# untitled.net
KiCad netlist of a schematic drawn in EAGLE
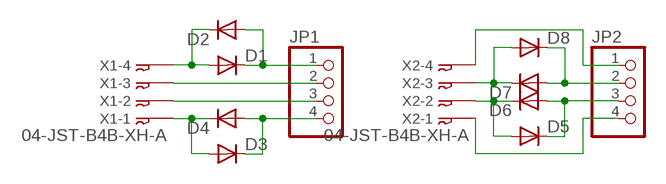
[diagram p0: schematic, sheet 1]

(export (version "E")
  (design (tool "Eeschema 10.0.6"))
  (components
    (comp (ref "D1")
      (value "DIODE-SMB")
      (footprint "eagle-import:SMB")
      (libsource (lib "eagle-import") (part "DIODE-SMB"))
    )
    (comp (ref "D2")
      (value "DIODE-SMB")
      (footprint "eagle-import:SMB")
      (libsource (lib "eagle-import") (part "DIODE-SMB"))
    )
    (comp (ref "D3")
      (value "DIODE-SMB")
      (footprint "eagle-import:SMB")
      (libsource (lib "eagle-import") (part "DIODE-SMB"))
    )
    (comp (ref "D4")
      (value "DIODE-SMB")
      (footprint "eagle-import:SMB")
      (libsource (lib "eagle-import") (part "DIODE-SMB"))
    )
    (comp (ref "D5")
      (value "DIODE-SMC")
      (footprint "eagle-import:SMC")
      (libsource (lib "eagle-import") (part "DIODE-SMC"))
    )
    (comp (ref "D6")
      (value "DIODE-SMC")
      (footprint "eagle-import:SMC")
      (libsource (lib "eagle-import") (part "DIODE-SMC"))
    )
    (comp (ref "D7")
      (value "DIODE-SMC")
      (footprint "eagle-import:SMC")
      (libsource (lib "eagle-import") (part "DIODE-SMC"))
    )
    (comp (ref "D8")
      (value "DIODE-SMC")
      (footprint "eagle-import:SMC")
      (libsource (lib "eagle-import") (part "DIODE-SMC"))
    )
    (comp (ref "JP1")
      (value "PINHD-1X4")
      (footprint "eagle-import:1X04")
      (libsource (lib "eagle-import") (part "PINHD-1X4"))
    )
    (comp (ref "JP2")
      (value "PINHD-1X4")
      (footprint "eagle-import:1X04")
      (libsource (lib "eagle-import") (part "PINHD-1X4"))
    )
    (comp (ref "X1")
      (value "04-JST-B4B-XH-A")
      (footprint "eagle-import:B4B-XH")
      (libsource (lib "eagle-import") (part "04-JST-B4B-XH-A"))
    )
    (comp (ref "X2")
      (value "04-JST-B4B-XH-A")
      (footprint "eagle-import:B4B-XH")
      (libsource (lib "eagle-import") (part "04-JST-B4B-XH-A"))
    )
  )
  (nets
    (net (code "1") (name "Net-(D1-PadC)") (class "Default")
      (node (ref "D1") (pin "C") (pinfunction "C_C") (pintype "passive"))
      (node (ref "D2") (pin "A") (pinfunction "A_A") (pintype "passive"))
      (node (ref "JP1") (pin "1") (pinfunction "1_1") (pintype "passive"))
    )
    (net (code "2") (name "Net-(D3-PadC)") (class "Default")
      (node (ref "D3") (pin "C") (pinfunction "C_C") (pintype "passive"))
      (node (ref "D4") (pin "A") (pinfunction "A_A") (pintype "passive"))
      (node (ref "JP1") (pin "4") (pinfunction "4_4") (pintype "passive"))
    )
    (net (code "3") (name "Net-(D5-PadC)") (class "Default")
      (node (ref "D5") (pin "C") (pinfunction "C_C") (pintype "passive"))
      (node (ref "D6") (pin "A") (pinfunction "A_A") (pintype "passive"))
      (node (ref "JP2") (pin "3") (pinfunction "3_3") (pintype "passive"))
    )
    (net (code "4") (name "Net-(D7-PadA)") (class "Default")
      (node (ref "D7") (pin "A") (pinfunction "A_A") (pintype "passive"))
      (node (ref "D8") (pin "C") (pinfunction "C_C") (pintype "passive"))
      (node (ref "JP2") (pin "2") (pinfunction "2_2") (pintype "passive"))
    )
    (net (code "5") (name "Net-(X1A-1)") (class "Default")
      (node (ref "D3") (pin "A") (pinfunction "A_A") (pintype "passive"))
      (node (ref "D4") (pin "C") (pinfunction "C_C") (pintype "passive"))
      (node (ref "X1") (pin "P$1") (pinfunction "1_P$1") (pintype "passive"))
    )
    (net (code "6") (name "Net-(X1B-1)") (class "Default")
      (node (ref "JP1") (pin "3") (pinfunction "3_3") (pintype "passive"))
      (node (ref "X1") (pin "P$2") (pinfunction "1_P$2") (pintype "passive"))
    )
    (net (code "7") (name "Net-(X1C-1)") (class "Default")
      (node (ref "JP1") (pin "2") (pinfunction "2_2") (pintype "passive"))
      (node (ref "X1") (pin "P$3") (pinfunction "1_P$3") (pintype "passive"))
    )
    (net (code "8") (name "Net-(X1D-1)") (class "Default")
      (node (ref "D1") (pin "A") (pinfunction "A_A") (pintype "passive"))
      (node (ref "D2") (pin "C") (pinfunction "C_C") (pintype "passive"))
      (node (ref "X1") (pin "P$4") (pinfunction "1_P$4") (pintype "passive"))
    )
    (net (code "9") (name "Net-(X2A-1)") (class "Default")
      (node (ref "JP2") (pin "4") (pinfunction "4_4") (pintype "passive"))
      (node (ref "X2") (pin "P$1") (pinfunction "1_P$1") (pintype "passive"))
    )
    (net (code "10") (name "Net-(X2B-1)") (class "Default")
      (node (ref "D5") (pin "A") (pinfunction "A_A") (pintype "passive"))
      (node (ref "D6") (pin "C") (pinfunction "C_C") (pintype "passive"))
      (node (ref "X2") (pin "P$2") (pinfunction "1_P$2") (pintype "passive"))
    )
    (net (code "11") (name "Net-(X2C-1)") (class "Default")
      (node (ref "D7") (pin "C") (pinfunction "C_C") (pintype "passive"))
      (node (ref "D8") (pin "A") (pinfunction "A_A") (pintype "passive"))
      (node (ref "X2") (pin "P$3") (pinfunction "1_P$3") (pintype "passive"))
    )
    (net (code "12") (name "Net-(X2D-1)") (class "Default")
      (node (ref "JP2") (pin "1") (pinfunction "1_1") (pintype "passive"))
      (node (ref "X2") (pin "P$4") (pinfunction "1_P$4") (pintype "passive"))
    )
  )
)
